# IPMC_MACP_2.net
KiCad netlist of a schematic drawn in Altium Designer
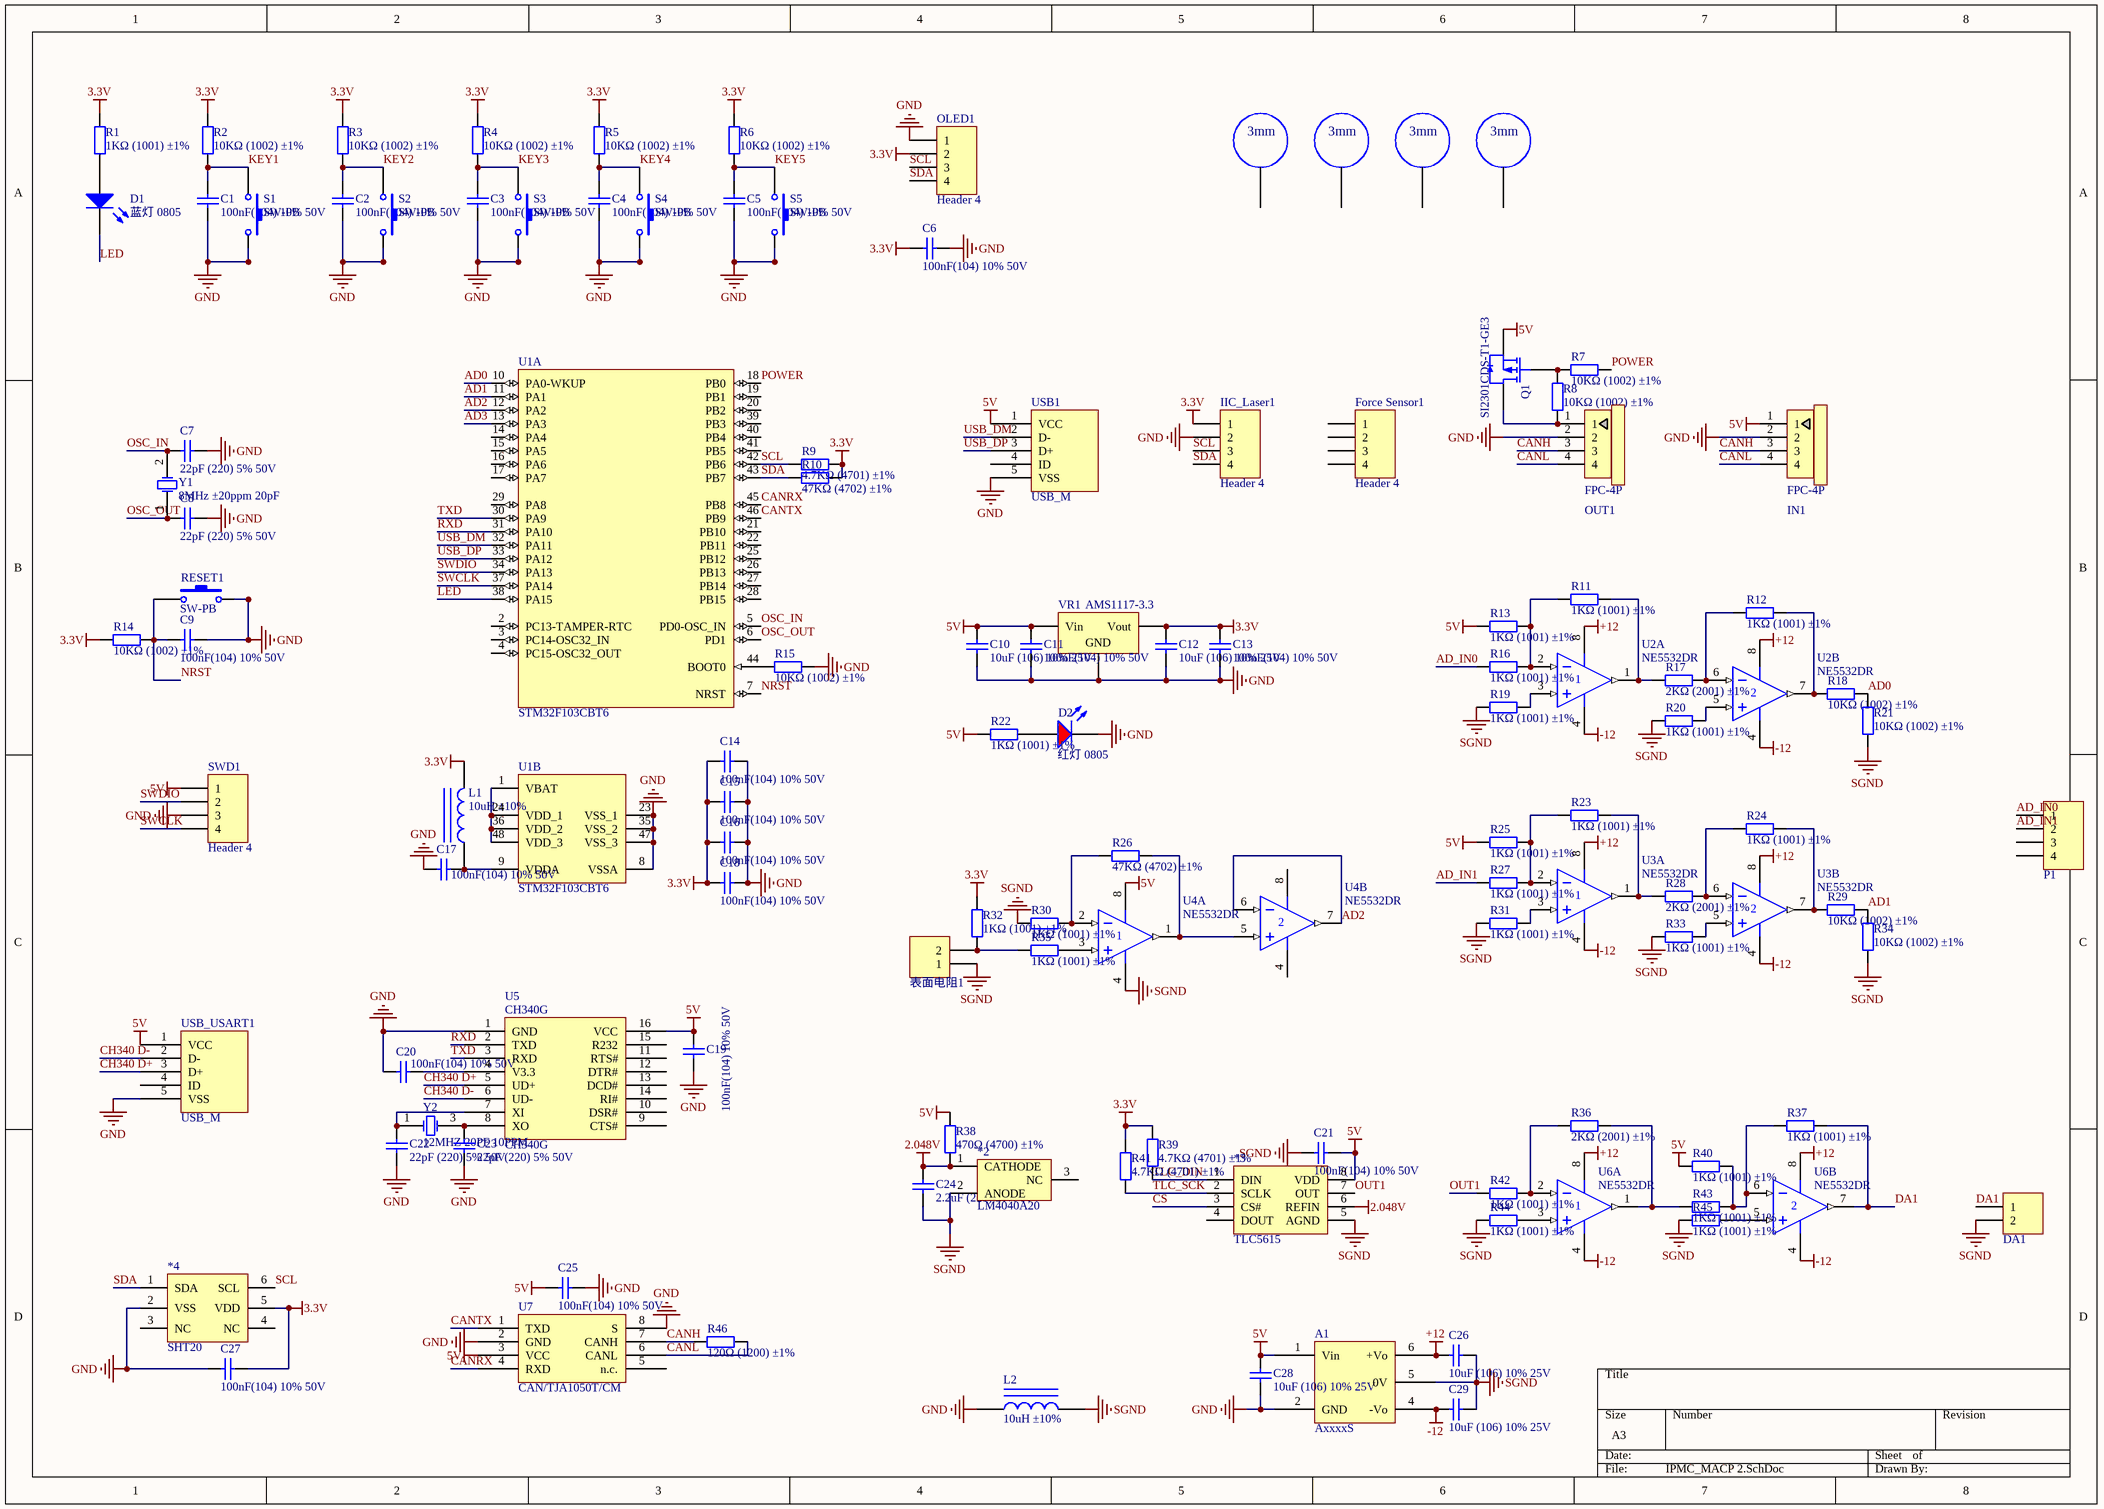
[diagram p0: IPMC_MACP 2.SchDoc]

(export (version "E")
  (design (tool "Eeschema 10.0.6"))
  (components
    (comp (ref "*2")
      (value "LM4040A20")
      (footprint "SOT-23")
      (description "2.048V基准电压芯片")
      (libsource (lib "fszhang") (part "LM4040A20"))
    )
    (comp (ref "*3")
      (value "TLC5615")
      (footprint "SOP-8")
      (description "单通道10bitDA数模转换器")
      (libsource (lib "fszhang") (part "TLC5615"))
    )
    (comp (ref "*4") (value "SHT20") (footprint "DFN6") (libsource (lib "fszhang") (part "SHT20")))
    (comp (ref "A1")
      (value "AxxxxS")
      (footprint "AxxxxS")
      (description "能达电源模块")
      (libsource (lib "fszhang") (part "AxxxxS"))
    )
    (comp (ref "C1")
      (value "100nF(104) 10% 50V")
      (footprint "0805_C")
      (description "贴片电容")
      (libsource (lib "Miscellaneous Devices LC") (part "0805 100nF(104) 10% 50V"))
    )
    (comp (ref "C2")
      (value "100nF(104) 10% 50V")
      (footprint "0805_C")
      (description "贴片电容")
      (libsource (lib "Miscellaneous Devices LC") (part "0805 100nF(104) 10% 50V"))
    )
    (comp (ref "C3")
      (value "100nF(104) 10% 50V")
      (footprint "0805_C")
      (description "贴片电容")
      (libsource (lib "Miscellaneous Devices LC") (part "0805 100nF(104) 10% 50V"))
    )
    (comp (ref "C4")
      (value "100nF(104) 10% 50V")
      (footprint "0805_C")
      (description "贴片电容")
      (libsource (lib "Miscellaneous Devices LC") (part "0805 100nF(104) 10% 50V"))
    )
    (comp (ref "C5")
      (value "100nF(104) 10% 50V")
      (footprint "0805_C")
      (description "贴片电容")
      (libsource (lib "Miscellaneous Devices LC") (part "0805 100nF(104) 10% 50V"))
    )
    (comp (ref "C6")
      (value "100nF(104) 10% 50V")
      (footprint "0805_C")
      (description "贴片电容")
      (libsource (lib "Miscellaneous Devices LC") (part "0805 100nF(104) 10% 50V"))
    )
    (comp (ref "C7")
      (value "22pF (220) 5% 50V")
      (footprint "0805_C")
      (description "贴片电容")
      (libsource (lib "Miscellaneous Devices LC") (part "0805 22pF (220) 5% 50V"))
    )
    (comp (ref "C8")
      (value "22pF (220) 5% 50V")
      (footprint "0805_C")
      (description "贴片电容")
      (libsource (lib "Miscellaneous Devices LC") (part "0805 22pF (220) 5% 50V"))
    )
    (comp (ref "C9")
      (value "100nF(104) 10% 50V")
      (footprint "0805_C")
      (description "贴片电容")
      (libsource (lib "Miscellaneous Devices LC") (part "0805 100nF(104) 10% 50V"))
    )
    (comp (ref "C10")
      (value "10uF (106) 10% 25V")
      (footprint "0805_C")
      (description "贴片电容")
      (libsource (lib "Miscellaneous Devices LC") (part "0805 10uF (106) 10% 25V"))
    )
    (comp (ref "C11")
      (value "100nF(104) 10% 50V")
      (footprint "0805_C")
      (description "贴片电容")
      (libsource (lib "Miscellaneous Devices LC") (part "0805 100nF(104) 10% 50V"))
    )
    (comp (ref "C12")
      (value "10uF (106) 10% 25V")
      (footprint "0805_C")
      (description "贴片电容")
      (libsource (lib "Miscellaneous Devices LC") (part "0805 10uF (106) 10% 25V"))
    )
    (comp (ref "C13")
      (value "100nF(104) 10% 50V")
      (footprint "0805_C")
      (description "贴片电容")
      (libsource (lib "Miscellaneous Devices LC") (part "0805 100nF(104) 10% 50V"))
    )
    (comp (ref "C14")
      (value "100nF(104) 10% 50V")
      (footprint "0805_C")
      (description "贴片电容")
      (libsource (lib "Miscellaneous Devices LC") (part "0805 100nF(104) 10% 50V"))
    )
    (comp (ref "C15")
      (value "100nF(104) 10% 50V")
      (footprint "0805_C")
      (description "贴片电容")
      (libsource (lib "Miscellaneous Devices LC") (part "0805 100nF(104) 10% 50V"))
    )
    (comp (ref "C16")
      (value "100nF(104) 10% 50V")
      (footprint "0805_C")
      (description "贴片电容")
      (libsource (lib "Miscellaneous Devices LC") (part "0805 100nF(104) 10% 50V"))
    )
    (comp (ref "C17")
      (value "100nF(104) 10% 50V")
      (footprint "0805_C")
      (description "贴片电容")
      (libsource (lib "Miscellaneous Devices LC") (part "0805 100nF(104) 10% 50V"))
    )
    (comp (ref "C18")
      (value "100nF(104) 10% 50V")
      (footprint "0805_C")
      (description "贴片电容")
      (libsource (lib "Miscellaneous Devices LC") (part "0805 100nF(104) 10% 50V"))
    )
    (comp (ref "C19")
      (value "100nF(104) 10% 50V")
      (footprint "0805_C")
      (description "贴片电容")
      (libsource (lib "Miscellaneous Devices LC") (part "0805 100nF(104) 10% 50V"))
    )
    (comp (ref "C20")
      (value "100nF(104) 10% 50V")
      (footprint "0805_C")
      (description "贴片电容")
      (libsource (lib "Miscellaneous Devices LC") (part "0805 100nF(104) 10% 50V"))
    )
    (comp (ref "C21")
      (value "100nF(104) 10% 50V")
      (footprint "0805_C")
      (description "贴片电容")
      (libsource (lib "Miscellaneous Devices LC") (part "0805 100nF(104) 10% 50V"))
    )
    (comp (ref "C22")
      (value "22pF (220) 5% 50V")
      (footprint "0805_C")
      (description "贴片电容")
      (libsource (lib "Miscellaneous Devices LC") (part "0805 22pF (220) 5% 50V"))
    )
    (comp (ref "C23")
      (value "22pF (220) 5% 50V")
      (footprint "0805_C")
      (description "贴片电容")
      (libsource (lib "Miscellaneous Devices LC") (part "0805 22pF (220) 5% 50V"))
    )
    (comp (ref "C24")
      (value "2.2uF (225) 20% 50V")
      (footprint "0805_C")
      (description "贴片电容")
      (libsource (lib "Miscellaneous Devices LC") (part "0805 2.2uF (225) 20% 50V"))
    )
    (comp (ref "C25")
      (value "100nF(104) 10% 50V")
      (footprint "0805_C")
      (description "贴片电容")
      (libsource (lib "Miscellaneous Devices LC") (part "0805 100nF(104) 10% 50V"))
    )
    (comp (ref "C26")
      (value "10uF (106) 10% 25V")
      (footprint "0805_C")
      (description "贴片电容")
      (libsource (lib "Miscellaneous Devices LC") (part "0805 10uF (106) 10% 25V"))
    )
    (comp (ref "C27")
      (value "100nF(104) 10% 50V")
      (footprint "0805_C")
      (description "贴片电容")
      (libsource (lib "Miscellaneous Devices LC") (part "0805 100nF(104) 10% 50V"))
    )
    (comp (ref "C28")
      (value "10uF (106) 10% 25V")
      (footprint "0805_C")
      (description "贴片电容")
      (libsource (lib "Miscellaneous Devices LC") (part "0805 10uF (106) 10% 25V"))
    )
    (comp (ref "C29")
      (value "10uF (106) 10% 25V")
      (footprint "0805_C")
      (description "贴片电容")
      (libsource (lib "Miscellaneous Devices LC") (part "0805 10uF (106) 10% 25V"))
    )
    (comp (ref "D1")
      (value "蓝灯 0805")
      (footprint "0805_LED_S1")
      (description "发光二极管")
      (libsource (lib "Miscellaneous Devices LC") (part "0805 蓝灯"))
    )
    (comp (ref "D2")
      (value "红灯 0805")
      (footprint "0805_LED_S1")
      (description "发光二极管")
      (libsource (lib "Miscellaneous Devices LC") (part "0805 红灯"))
    )
    (comp (ref "DA1")
      (value "Header 2")
      (footprint "HDR2X1_A")
      (description "接插件")
      (libsource (lib "fszhang") (part "Header 2"))
    )
    (comp (ref "Force Sensor1")
      (value "Header 4")
      (footprint "HDR1X4")
      (description "Header, 4-Pin")
      (libsource (lib "Miscellaneous Connectors") (part "Header 4"))
    )
    (comp (ref "IIC_Laser1")
      (value "Header 4")
      (footprint "HDR1X4")
      (description "Header, 4-Pin")
      (libsource (lib "Miscellaneous Connectors") (part "Header 4"))
    )
    (comp (ref "IN1")
      (value "FPC-4P")
      (footprint "FPC1.0-4P-A")
      (description "FPC排线连接器")
      (libsource (lib "fszhang") (part "FPC-4P"))
    )
    (comp (ref "L1")
      (value "10uH ±10%")
      (footprint "0805_L")
      (description "贴片电感")
      (libsource (lib "Miscellaneous Devices LC") (part "0805 10uH 10%"))
    )
    (comp (ref "L2")
      (value "10uH ±10%")
      (footprint "0805_L")
      (description "贴片电感")
      (libsource (lib "Miscellaneous Devices LC") (part "0805 10uH 10%"))
    )
    (comp (ref "OLED1")
      (value "Header 4")
      (footprint "HDR1X4")
      (description "Header, 4-Pin")
      (libsource (lib "Miscellaneous Connectors") (part "Header 4"))
    )
    (comp (ref "OUT1")
      (value "FPC-4P")
      (footprint "FPC1.0-4P-A")
      (description "FPC排线连接器")
      (libsource (lib "fszhang") (part "FPC-4P"))
    )
    (comp (ref "P1")
      (value "Header 4")
      (footprint "HDR4X1_A")
      (description "接插件")
      (libsource (lib "fszhang") (part "Header 4"))
    )
    (comp (ref "Q1")
      (value "SI2301CDS-T1-GE3")
      (footprint "SOT-23(SOT-23-3)")
      (description "MOS(场效应管)")
      (libsource (lib "Miscellaneous Devices LC") (part "SI2301CDS-T1-GE3"))
    )
    (comp (ref "R1")
      (value "1KΩ (1001) ±1%")
      (footprint "0805_R")
      (description "贴片电阻")
      (libsource (lib "") (part "0805 1KΩ (1001) 1%_1"))
    )
    (comp (ref "R2")
      (value "10KΩ (1002) ±1%")
      (footprint "0805_R")
      (description "贴片电阻")
      (libsource (lib "Miscellaneous Devices LC") (part "0805 10KΩ (1002) 1%"))
    )
    (comp (ref "R3")
      (value "10KΩ (1002) ±1%")
      (footprint "0805_R")
      (description "贴片电阻")
      (libsource (lib "Miscellaneous Devices LC") (part "0805 10KΩ (1002) 1%"))
    )
    (comp (ref "R4")
      (value "10KΩ (1002) ±1%")
      (footprint "0805_R")
      (description "贴片电阻")
      (libsource (lib "Miscellaneous Devices LC") (part "0805 10KΩ (1002) 1%"))
    )
    (comp (ref "R5")
      (value "10KΩ (1002) ±1%")
      (footprint "0805_R")
      (description "贴片电阻")
      (libsource (lib "Miscellaneous Devices LC") (part "0805 10KΩ (1002) 1%"))
    )
    (comp (ref "R6")
      (value "10KΩ (1002) ±1%")
      (footprint "0805_R")
      (description "贴片电阻")
      (libsource (lib "Miscellaneous Devices LC") (part "0805 10KΩ (1002) 1%"))
    )
    (comp (ref "R7")
      (value "10KΩ (1002) ±1%")
      (footprint "0805_R")
      (description "贴片电阻")
      (libsource (lib "") (part "0805 10KΩ (1002) 1%_1"))
    )
    (comp (ref "R8")
      (value "10KΩ (1002) ±1%")
      (footprint "0805_R")
      (description "贴片电阻")
      (libsource (lib "Miscellaneous Devices LC") (part "0805 10KΩ (1002) 1%"))
    )
    (comp (ref "R9")
      (value "4.7KΩ (4701) ±1%")
      (footprint "0805_R")
      (description "贴片电阻")
      (libsource (lib "") (part "0805 4.7KΩ (4701) 1%_1"))
    )
    (comp (ref "R10")
      (value "47KΩ (4702) ±1%")
      (footprint "0805_R")
      (description "贴片电阻")
      (libsource (lib "Miscellaneous Devices LC") (part "0805 47KΩ (4702) 1%"))
    )
    (comp (ref "R11")
      (value "1KΩ (1001) ±1%")
      (footprint "0805_R")
      (description "贴片电阻")
      (libsource (lib "") (part "0805 1KΩ (1001) 1%_2"))
    )
    (comp (ref "R12")
      (value "1KΩ (1001) ±1%")
      (footprint "0805_R")
      (description "贴片电阻")
      (libsource (lib "") (part "0805 1KΩ (1001) 1%_2"))
    )
    (comp (ref "R13")
      (value "1KΩ (1001) ±1%")
      (footprint "0805_R")
      (description "贴片电阻")
      (libsource (lib "") (part "0805 1KΩ (1001) 1%_2"))
    )
    (comp (ref "R14")
      (value "10KΩ (1002) ±1%")
      (footprint "0805_R")
      (description "贴片电阻")
      (libsource (lib "") (part "0805 10KΩ (1002) 1%_1"))
    )
    (comp (ref "R15")
      (value "10KΩ (1002) ±1%")
      (footprint "0805_R")
      (description "贴片电阻")
      (libsource (lib "") (part "0805 10KΩ (1002) 1%_1"))
    )
    (comp (ref "R16")
      (value "1KΩ (1001) ±1%")
      (footprint "0805_R")
      (description "贴片电阻")
      (libsource (lib "") (part "0805 1KΩ (1001) 1%_2"))
    )
    (comp (ref "R17")
      (value "2KΩ (2001) ±1%")
      (footprint "0805_R")
      (description "贴片电阻")
      (libsource (lib "Miscellaneous Devices LC") (part "0805 2KΩ (2001) 1%"))
    )
    (comp (ref "R18")
      (value "10KΩ (1002) ±1%")
      (footprint "0805_R")
      (description "贴片电阻")
      (libsource (lib "") (part "0805 10KΩ (1002) 1%_1"))
    )
    (comp (ref "R19")
      (value "1KΩ (1001) ±1%")
      (footprint "0805_R")
      (description "贴片电阻")
      (libsource (lib "") (part "0805 1KΩ (1001) 1%_2"))
    )
    (comp (ref "R20")
      (value "1KΩ (1001) ±1%")
      (footprint "0805_R")
      (description "贴片电阻")
      (libsource (lib "") (part "0805 1KΩ (1001) 1%_2"))
    )
    (comp (ref "R21")
      (value "10KΩ (1002) ±1%")
      (footprint "0805_R")
      (description "贴片电阻")
      (libsource (lib "") (part "0805 10KΩ (1002) 1%_2"))
    )
    (comp (ref "R22")
      (value "1KΩ (1001) ±1%")
      (footprint "0805_R")
      (description "贴片电阻")
      (libsource (lib "Miscellaneous Devices LC") (part "0805 1KΩ (1001) 1%"))
    )
    (comp (ref "R23")
      (value "1KΩ (1001) ±1%")
      (footprint "0805_R")
      (description "贴片电阻")
      (libsource (lib "") (part "0805 1KΩ (1001) 1%_2"))
    )
    (comp (ref "R24")
      (value "1KΩ (1001) ±1%")
      (footprint "0805_R")
      (description "贴片电阻")
      (libsource (lib "") (part "0805 1KΩ (1001) 1%_2"))
    )
    (comp (ref "R25")
      (value "1KΩ (1001) ±1%")
      (footprint "0805_R")
      (description "贴片电阻")
      (libsource (lib "") (part "0805 1KΩ (1001) 1%_2"))
    )
    (comp (ref "R26")
      (value "47KΩ (4702) ±1%")
      (footprint "0805_R")
      (description "贴片电阻")
      (libsource (lib "Miscellaneous Devices LC") (part "0805 47KΩ (4702) 1%"))
    )
    (comp (ref "R27")
      (value "1KΩ (1001) ±1%")
      (footprint "0805_R")
      (description "贴片电阻")
      (libsource (lib "") (part "0805 1KΩ (1001) 1%_2"))
    )
    (comp (ref "R28")
      (value "2KΩ (2001) ±1%")
      (footprint "0805_R")
      (description "贴片电阻")
      (libsource (lib "Miscellaneous Devices LC") (part "0805 2KΩ (2001) 1%"))
    )
    (comp (ref "R29")
      (value "10KΩ (1002) ±1%")
      (footprint "0805_R")
      (description "贴片电阻")
      (libsource (lib "") (part "0805 10KΩ (1002) 1%_1"))
    )
    (comp (ref "R30")
      (value "1KΩ (1001) ±1%")
      (footprint "0805_R")
      (description "贴片电阻")
      (libsource (lib "Miscellaneous Devices LC") (part "0805 1KΩ (1001) 1%"))
    )
    (comp (ref "R31")
      (value "1KΩ (1001) ±1%")
      (footprint "0805_R")
      (description "贴片电阻")
      (libsource (lib "") (part "0805 1KΩ (1001) 1%_2"))
    )
    (comp (ref "R32")
      (value "1KΩ (1001) ±1%")
      (footprint "0805_R")
      (description "贴片电阻")
      (libsource (lib "") (part "0805 1KΩ (1001) 1%_1"))
    )
    (comp (ref "R33")
      (value "1KΩ (1001) ±1%")
      (footprint "0805_R")
      (description "贴片电阻")
      (libsource (lib "") (part "0805 1KΩ (1001) 1%_2"))
    )
    (comp (ref "R34")
      (value "10KΩ (1002) ±1%")
      (footprint "0805_R")
      (description "贴片电阻")
      (libsource (lib "") (part "0805 10KΩ (1002) 1%_2"))
    )
    (comp (ref "R35")
      (value "1KΩ (1001) ±1%")
      (footprint "0805_R")
      (description "贴片电阻")
      (libsource (lib "Miscellaneous Devices LC") (part "0805 1KΩ (1001) 1%"))
    )
    (comp (ref "R36")
      (value "2KΩ (2001) ±1%")
      (footprint "0805_R")
      (description "贴片电阻")
      (libsource (lib "Miscellaneous Devices LC") (part "0805 2KΩ (2001) 1%"))
    )
    (comp (ref "R37")
      (value "1KΩ (1001) ±1%")
      (footprint "0805_R")
      (description "贴片电阻")
      (libsource (lib "") (part "0805 1KΩ (1001) 1%_2"))
    )
    (comp (ref "R38")
      (value "470Ω (4700) ±1%")
      (footprint "0805_R")
      (description "贴片电阻")
      (libsource (lib "Miscellaneous Devices LC") (part "0805 470Ω (4700) 1%"))
    )
    (comp (ref "R39")
      (value "4.7KΩ (4701) ±1%")
      (footprint "0805_R")
      (description "贴片电阻")
      (libsource (lib "Miscellaneous Devices LC") (part "0805 4.7KΩ (4701) 1%"))
    )
    (comp (ref "R40")
      (value "1KΩ (1001) ±1%")
      (footprint "0805_R")
      (description "贴片电阻")
      (libsource (lib "") (part "0805 1KΩ (1001) 1%_2"))
    )
    (comp (ref "R41")
      (value "4.7KΩ (4701) ±1%")
      (footprint "0805_R")
      (description "贴片电阻")
      (libsource (lib "Miscellaneous Devices LC") (part "0805 4.7KΩ (4701) 1%"))
    )
    (comp (ref "R42")
      (value "1KΩ (1001) ±1%")
      (footprint "0805_R")
      (description "贴片电阻")
      (libsource (lib "") (part "0805 1KΩ (1001) 1%_2"))
    )
    (comp (ref "R43")
      (value "1KΩ (1001) ±1%")
      (footprint "0805_R")
      (description "贴片电阻")
      (libsource (lib "") (part "0805 1KΩ (1001) 1%_2"))
    )
    (comp (ref "R44")
      (value "1KΩ (1001) ±1%")
      (footprint "0805_R")
      (description "贴片电阻")
      (libsource (lib "") (part "0805 1KΩ (1001) 1%_2"))
    )
    (comp (ref "R45")
      (value "1KΩ (1001) ±1%")
      (footprint "0805_R")
      (description "贴片电阻")
      (libsource (lib "") (part "0805 1KΩ (1001) 1%_2"))
    )
    (comp (ref "R46")
      (value "120Ω (1200) ±1%")
      (footprint "0805_R")
      (description "贴片电阻")
      (libsource (lib "Miscellaneous Devices LC") (part "0805 120Ω (1200) 1%"))
    )
    (comp (ref "RESET1")
      (value "SW-PB")
      (footprint "SW_PB2_A1")
      (description "微动开关")
      (libsource (lib "fszhang") (part "SW-PB"))
    )
    (comp (ref "S1")
      (value "SW-PB")
      (footprint "SW_PB2_A1")
      (description "微动开关")
      (libsource (lib "fszhang") (part "SW-PB"))
    )
    (comp (ref "S2")
      (value "SW-PB")
      (footprint "SW_PB2_A1")
      (description "微动开关")
      (libsource (lib "fszhang") (part "SW-PB"))
    )
    (comp (ref "S3")
      (value "SW-PB")
      (footprint "SW_PB2_A1")
      (description "微动开关")
      (libsource (lib "fszhang") (part "SW-PB"))
    )
    (comp (ref "S4")
      (value "SW-PB")
      (footprint "SW_PB2_A1")
      (description "微动开关")
      (libsource (lib "fszhang") (part "SW-PB"))
    )
    (comp (ref "S5")
      (value "SW-PB")
      (footprint "SW_PB2_A1")
      (description "微动开关")
      (libsource (lib "fszhang") (part "SW-PB"))
    )
    (comp (ref "SWD1")
      (value "Header 4")
      (footprint "HDR1X4")
      (description "Header, 4-Pin")
      (libsource (lib "Miscellaneous Connectors") (part "Header 4"))
    )
    (comp (ref "T1") (value "M3铜柱螺丝孔") (footprint "螺丝孔-3mm") (libsource (lib "fszhang") (part "M3铜柱螺丝孔")))
    (comp (ref "T2") (value "M3铜柱螺丝孔") (footprint "螺丝孔-3mm") (libsource (lib "fszhang") (part "M3铜柱螺丝孔")))
    (comp (ref "T3") (value "M3铜柱螺丝孔") (footprint "螺丝孔-3mm") (libsource (lib "fszhang") (part "M3铜柱螺丝孔")))
    (comp (ref "T4") (value "M3铜柱螺丝孔") (footprint "螺丝孔-3mm") (libsource (lib "fszhang") (part "M3铜柱螺丝孔")))
    (comp (ref "U1")
      (value "STM32F103CBT6")
      (footprint "LQFP-48_7x7x05P")
      (description "ARM")
      (libsource (lib "Miscellaneous Devices LC") (part "STM32F103CBT6"))
    )
    (comp (ref "U2")
      (value "NE5532DR")
      (footprint "SOIC-8_150mil")
      (description "功放")
      (libsource (lib "Miscellaneous Devices LC") (part "NE5532DR"))
    )
    (comp (ref "U3")
      (value "NE5532DR")
      (footprint "SOIC-8_150mil")
      (description "功放")
      (libsource (lib "Miscellaneous Devices LC") (part "NE5532DR"))
    )
    (comp (ref "U4")
      (value "NE5532DR")
      (footprint "SOIC-8_150mil")
      (description "功放")
      (libsource (lib "Miscellaneous Devices LC") (part "NE5532DR"))
    )
    (comp (ref "U5")
      (value "CH340G")
      (footprint "SOIC-16_150mil")
      (description "USB")
      (libsource (lib "Miscellaneous Devices LC") (part "CH340G"))
    )
    (comp (ref "U6")
      (value "NE5532DR")
      (footprint "SOIC-8_150mil")
      (description "功放")
      (libsource (lib "Miscellaneous Devices LC") (part "NE5532DR"))
    )
    (comp (ref "U7")
      (value "CAN/TJA1050T/CM")
      (footprint "SOIC-8_150mil")
      (description "CAN")
      (libsource (lib "Miscellaneous Devices LC") (part "CAN/TJA1050T/CM"))
    )
    (comp (ref "USB1")
      (value "USB_M")
      (footprint "USB_MICRO")
      (description "MicroUSB接口")
      (libsource (lib "fszhang") (part "USB_M"))
    )
    (comp (ref "USB_USART1")
      (value "USB_M")
      (footprint "USB_MICRO")
      (description "MicroUSB接口")
      (libsource (lib "fszhang") (part "USB_M"))
    )
    (comp (ref "VR1")
      (value "AMS1117-3.3")
      (footprint "SOT-223")
      (description "低压差线性稳压(LDO)")
      (libsource (lib "Miscellaneous Devices LC") (part "SOT-223 AMS1117-3.3"))
    )
    (comp (ref "Y1")
      (value "8MHz ±20ppm 20pF")
      (footprint "SMD-5032_2P")
      (description "贴片晶振")
      (libsource (lib "Miscellaneous Devices LC") (part "SMD-5032_2P 8MHz 20ppm 20pF"))
    )
    (comp (ref "Y2")
      (value "12MHZ 20PF 10PPM")
      (footprint "SMD-3225_4P")
      (description "贴片晶振")
      (libsource (lib "Miscellaneous Devices LC") (part "SMD-3225_4P  12MHZ 20PF 10PPM"))
    )
    (comp (ref "表面电阻1")
      (value "Header 2")
      (footprint "HDR2X1_A")
      (description "接插件")
      (libsource (lib "") (part "Header 2_1"))
    )
  )
  (nets
    (net (code "1") (name "+12") (class "Default")
      (node (ref "A1") (pin "6") (pinfunction "+Vo_6") (pintype "passive"))
      (node (ref "C26") (pin "1") (pinfunction "1_1") (pintype "passive"))
      (node (ref "U2") (pin "8") (pinfunction "V+_8") (pintype "power_in"))
      (node (ref "U3") (pin "8") (pinfunction "V+_8") (pintype "power_in"))
      (node (ref "U6") (pin "8") (pinfunction "V+_8") (pintype "power_in"))
    )
    (net (code "2") (name "-12") (class "Default")
      (node (ref "A1") (pin "4") (pinfunction "-Vo_4") (pintype "passive"))
      (node (ref "C29") (pin "1") (pinfunction "1_1") (pintype "passive"))
      (node (ref "U2") (pin "4") (pinfunction "V-_4") (pintype "power_in"))
      (node (ref "U3") (pin "4") (pinfunction "V-_4") (pintype "power_in"))
      (node (ref "U6") (pin "4") (pinfunction "V-_4") (pintype "power_in"))
    )
    (net (code "3") (name "/AD0") (class "Default")
      (node (ref "R18") (pin "2") (pinfunction "2_2") (pintype "passive"))
      (node (ref "R21") (pin "2") (pinfunction "2_2") (pintype "passive"))
      (node (ref "U1") (pin "10") (pinfunction "PA0-WKUP_10") (pintype "bidirectional"))
    )
    (net (code "4") (name "/AD1") (class "Default")
      (node (ref "R29") (pin "2") (pinfunction "2_2") (pintype "passive"))
      (node (ref "R34") (pin "2") (pinfunction "2_2") (pintype "passive"))
      (node (ref "U1") (pin "11") (pinfunction "PA1_11") (pintype "bidirectional"))
    )
    (net (code "5") (name "/AD2") (class "Default")
      (node (ref "U1") (pin "12") (pinfunction "PA2_12") (pintype "bidirectional"))
      (node (ref "U4") (pin "6") (pinfunction "IN-_6") (pintype "input"))
      (node (ref "U4") (pin "7") (pinfunction "OUT_7") (pintype "output"))
    )
    (net (code "6") (name "/AD3") (class "Default")
      (node (ref "U1") (pin "13") (pinfunction "PA3_13") (pintype "bidirectional"))
    )
    (net (code "7") (name "/AD_IN0") (class "Default")
      (node (ref "P1") (pin "1") (pinfunction "1_1") (pintype "passive"))
      (node (ref "R16") (pin "2") (pinfunction "2_2") (pintype "passive"))
    )
    (net (code "8") (name "/AD_IN1") (class "Default")
      (node (ref "P1") (pin "2") (pinfunction "2_2") (pintype "passive"))
      (node (ref "R27") (pin "2") (pinfunction "2_2") (pintype "passive"))
    )
    (net (code "9") (name "/CANH") (class "Default")
      (node (ref "IN1") (pin "3") (pinfunction "3_3") (pintype "passive"))
      (node (ref "OUT1") (pin "3") (pinfunction "3_3") (pintype "passive"))
      (node (ref "R46") (pin "1") (pinfunction "1_1") (pintype "passive"))
      (node (ref "U7") (pin "7") (pinfunction "CANH_7") (pintype "passive"))
    )
    (net (code "10") (name "/CANL") (class "Default")
      (node (ref "IN1") (pin "4") (pinfunction "4_4") (pintype "passive"))
      (node (ref "OUT1") (pin "4") (pinfunction "4_4") (pintype "passive"))
      (node (ref "R46") (pin "2") (pinfunction "2_2") (pintype "passive"))
      (node (ref "U7") (pin "6") (pinfunction "CANL_6") (pintype "passive"))
    )
    (net (code "11") (name "/CANRX") (class "Default")
      (node (ref "U1") (pin "45") (pinfunction "PB8_45") (pintype "bidirectional"))
      (node (ref "U7") (pin "4") (pinfunction "RXD_4") (pintype "passive"))
    )
    (net (code "12") (name "/CANTX") (class "Default")
      (node (ref "U1") (pin "46") (pinfunction "PB9_46") (pintype "bidirectional"))
      (node (ref "U7") (pin "1") (pinfunction "TXD_1") (pintype "passive"))
    )
    (net (code "13") (name "/CH340 D+") (class "Default")
      (node (ref "U5") (pin "5") (pinfunction "UD+_5") (pintype "passive"))
      (node (ref "USB_USART1") (pin "3") (pinfunction "D+_3") (pintype "passive"))
    )
    (net (code "14") (name "/CH340 D-") (class "Default")
      (node (ref "U5") (pin "6") (pinfunction "UD-_6") (pintype "passive"))
      (node (ref "USB_USART1") (pin "2") (pinfunction "D-_2") (pintype "passive"))
    )
    (net (code "15") (name "/CS") (class "Default")
      (node (ref "*3") (pin "3") (pinfunction "CS#_3") (pintype "passive"))
    )
    (net (code "16") (name "/DA1") (class "Default")
      (node (ref "DA1") (pin "1") (pinfunction "1_1") (pintype "passive"))
      (node (ref "R37") (pin "1") (pinfunction "1_1") (pintype "passive"))
      (node (ref "U6") (pin "7") (pinfunction "OUT_7") (pintype "output"))
    )
    (net (code "17") (name "/KEY1") (class "Default")
      (node (ref "C1") (pin "1") (pinfunction "1_1") (pintype "passive"))
      (node (ref "R2") (pin "2") (pinfunction "2_2") (pintype "passive"))
      (node (ref "S1") (pin "1") (pinfunction "1_1") (pintype "passive"))
    )
    (net (code "18") (name "/KEY2") (class "Default")
      (node (ref "C2") (pin "1") (pinfunction "1_1") (pintype "passive"))
      (node (ref "R3") (pin "2") (pinfunction "2_2") (pintype "passive"))
      (node (ref "S2") (pin "1") (pinfunction "1_1") (pintype "passive"))
    )
    (net (code "19") (name "/KEY3") (class "Default")
      (node (ref "C3") (pin "1") (pinfunction "1_1") (pintype "passive"))
      (node (ref "R4") (pin "2") (pinfunction "2_2") (pintype "passive"))
      (node (ref "S3") (pin "1") (pinfunction "1_1") (pintype "passive"))
    )
    (net (code "20") (name "/KEY4") (class "Default")
      (node (ref "C4") (pin "1") (pinfunction "1_1") (pintype "passive"))
      (node (ref "R5") (pin "2") (pinfunction "2_2") (pintype "passive"))
      (node (ref "S4") (pin "1") (pinfunction "1_1") (pintype "passive"))
    )
    (net (code "21") (name "/KEY5") (class "Default")
      (node (ref "C5") (pin "1") (pinfunction "1_1") (pintype "passive"))
      (node (ref "R6") (pin "2") (pinfunction "2_2") (pintype "passive"))
      (node (ref "S5") (pin "1") (pinfunction "1_1") (pintype "passive"))
    )
    (net (code "22") (name "/LED") (class "Default")
      (node (ref "D1") (pin "K") (pinfunction "K_K") (pintype "passive"))
      (node (ref "U1") (pin "38") (pinfunction "PA15_38") (pintype "bidirectional"))
    )
    (net (code "23") (name "/NRST") (class "Default")
      (node (ref "C9") (pin "1") (pinfunction "1_1") (pintype "passive"))
      (node (ref "R14") (pin "2") (pinfunction "2_2") (pintype "passive"))
      (node (ref "RESET1") (pin "1") (pinfunction "1_1") (pintype "passive"))
      (node (ref "U1") (pin "7") (pinfunction "NRST_7") (pintype "bidirectional"))
    )
    (net (code "24") (name "/OSC_IN") (class "Default")
      (node (ref "C7") (pin "2") (pinfunction "2_2") (pintype "passive"))
      (node (ref "U1") (pin "5") (pinfunction "PD0-OSC_IN_5") (pintype "bidirectional"))
      (node (ref "Y1") (pin "2") (pinfunction "OSC2_2") (pintype "passive"))
    )
    (net (code "25") (name "/OSC_OUT") (class "Default")
      (node (ref "C8") (pin "2") (pinfunction "2_2") (pintype "passive"))
      (node (ref "U1") (pin "6") (pinfunction "PD1_6") (pintype "bidirectional"))
      (node (ref "Y1") (pin "1") (pinfunction "OSC1_1") (pintype "passive"))
    )
    (net (code "26") (name "/OUT1") (class "Default")
      (node (ref "*3") (pin "7") (pinfunction "OUT_7") (pintype "passive"))
      (node (ref "R42") (pin "2") (pinfunction "2_2") (pintype "passive"))
    )
    (net (code "27") (name "/POWER") (class "Default")
      (node (ref "R7") (pin "2") (pinfunction "2_2") (pintype "passive"))
      (node (ref "U1") (pin "18") (pinfunction "PB0_18") (pintype "bidirectional"))
    )
    (net (code "28") (name "/RXD") (class "Default")
      (node (ref "U1") (pin "31") (pinfunction "PA10_31") (pintype "bidirectional"))
      (node (ref "U5") (pin "2") (pinfunction "TXD_2") (pintype "passive"))
    )
    (net (code "29") (name "/SCL") (class "Default")
      (node (ref "*4") (pin "6") (pinfunction "SCL_6") (pintype "passive"))
      (node (ref "IIC_Laser1") (pin "3") (pinfunction "3_3") (pintype "passive"))
      (node (ref "OLED1") (pin "3") (pinfunction "3_3") (pintype "passive"))
      (node (ref "R9") (pin "1") (pinfunction "1_1") (pintype "passive"))
      (node (ref "U1") (pin "42") (pinfunction "PB6_42") (pintype "bidirectional"))
    )
    (net (code "30") (name "/SDA") (class "Default")
      (node (ref "*4") (pin "1") (pinfunction "SDA_1") (pintype "passive"))
      (node (ref "IIC_Laser1") (pin "4") (pinfunction "4_4") (pintype "passive"))
      (node (ref "OLED1") (pin "4") (pinfunction "4_4") (pintype "passive"))
      (node (ref "R10") (pin "1") (pinfunction "1_1") (pintype "passive"))
      (node (ref "U1") (pin "43") (pinfunction "PB7_43") (pintype "bidirectional"))
    )
    (net (code "31") (name "/SWCLK") (class "Default")
      (node (ref "SWD1") (pin "4") (pinfunction "4_4") (pintype "passive"))
      (node (ref "U1") (pin "37") (pinfunction "PA14_37") (pintype "bidirectional"))
    )
    (net (code "32") (name "/SWDIO") (class "Default")
      (node (ref "SWD1") (pin "2") (pinfunction "2_2") (pintype "passive"))
      (node (ref "U1") (pin "34") (pinfunction "PA13_34") (pintype "bidirectional"))
    )
    (net (code "33") (name "/TLC_DIN") (class "Default")
      (node (ref "*3") (pin "1") (pinfunction "DIN_1") (pintype "passive"))
      (node (ref "R39") (pin "1") (pinfunction "1_1") (pintype "passive"))
    )
    (net (code "34") (name "/TLC_SCK") (class "Default")
      (node (ref "*3") (pin "2") (pinfunction "SCLK_2") (pintype "passive"))
      (node (ref "R41") (pin "1") (pinfunction "1_1") (pintype "passive"))
    )
    (net (code "35") (name "/TXD") (class "Default")
      (node (ref "U1") (pin "30") (pinfunction "PA9_30") (pintype "bidirectional"))
      (node (ref "U5") (pin "3") (pinfunction "RXD_3") (pintype "passive"))
    )
    (net (code "36") (name "/USB_DM") (class "Default")
      (node (ref "U1") (pin "32") (pinfunction "PA11_32") (pintype "bidirectional"))
      (node (ref "USB1") (pin "2") (pinfunction "D-_2") (pintype "passive"))
    )
    (net (code "37") (name "/USB_DP") (class "Default")
      (node (ref "U1") (pin "33") (pinfunction "PA12_33") (pintype "bidirectional"))
      (node (ref "USB1") (pin "3") (pinfunction "D+_3") (pintype "passive"))
    )
    (net (code "38") (name "2.048V") (class "Default")
      (node (ref "*2") (pin "1") (pinfunction "CATHODE_1") (pintype "passive"))
      (node (ref "*3") (pin "6") (pinfunction "REFIN_6") (pintype "passive"))
      (node (ref "C24") (pin "2") (pinfunction "2_2") (pintype "passive"))
      (node (ref "R38") (pin "1") (pinfunction "1_1") (pintype "passive"))
    )
    (net (code "39") (name "3.3V") (class "Default")
      (node (ref "*4") (pin "5") (pinfunction "VDD_5") (pintype "passive"))
      (node (ref "C12") (pin "2") (pinfunction "2_2") (pintype "passive"))
      (node (ref "C13") (pin "2") (pinfunction "2_2") (pintype "passive"))
      (node (ref "C14") (pin "2") (pinfunction "2_2") (pintype "passive"))
      (node (ref "C15") (pin "2") (pinfunction "2_2") (pintype "passive"))
      (node (ref "C16") (pin "2") (pinfunction "2_2") (pintype "passive"))
      (node (ref "C18") (pin "2") (pinfunction "2_2") (pintype "passive"))
      (node (ref "C27") (pin "2") (pinfunction "2_2") (pintype "passive"))
      (node (ref "C6") (pin "2") (pinfunction "2_2") (pintype "passive"))
      (node (ref "IIC_Laser1") (pin "1") (pinfunction "1_1") (pintype "passive"))
      (node (ref "L1") (pin "2") (pinfunction "2_2") (pintype "passive"))
      (node (ref "OLED1") (pin "2") (pinfunction "2_2") (pintype "passive"))
      (node (ref "R1") (pin "1") (pinfunction "1_1") (pintype "passive"))
      (node (ref "R10") (pin "2") (pinfunction "2_2") (pintype "passive"))
      (node (ref "R14") (pin "1") (pinfunction "1_1") (pintype "passive"))
      (node (ref "R2") (pin "1") (pinfunction "1_1") (pintype "passive"))
      (node (ref "R3") (pin "1") (pinfunction "1_1") (pintype "passive"))
      (node (ref "R32") (pin "1") (pinfunction "1_1") (pintype "passive"))
      (node (ref "R39") (pin "2") (pinfunction "2_2") (pintype "passive"))
      (node (ref "R4") (pin "1") (pinfunction "1_1") (pintype "passive"))
      (node (ref "R41") (pin "2") (pinfunction "2_2") (pintype "passive"))
      (node (ref "R5") (pin "1") (pinfunction "1_1") (pintype "passive"))
      (node (ref "R6") (pin "1") (pinfunction "1_1") (pintype "passive"))
      (node (ref "R9") (pin "2") (pinfunction "2_2") (pintype "passive"))
      (node (ref "VR1") (pin "2") (pinfunction "Vout_2") (pintype "passive"))
    )
    (net (code "40") (name "5V") (class "Default")
      (node (ref "*3") (pin "8") (pinfunction "VDD_8") (pintype "passive"))
      (node (ref "A1") (pin "1") (pinfunction "Vin_1") (pintype "passive"))
      (node (ref "C10") (pin "2") (pinfunction "2_2") (pintype "passive"))
      (node (ref "C11") (pin "2") (pinfunction "2_2") (pintype "passive"))
      (node (ref "C19") (pin "2") (pinfunction "2_2") (pintype "passive"))
      (node (ref "C21") (pin "1") (pinfunction "1_1") (pintype "passive"))
      (node (ref "C25") (pin "2") (pinfunction "2_2") (pintype "passive"))
      (node (ref "C28") (pin "2") (pinfunction "2_2") (pintype "passive"))
      (node (ref "IN1") (pin "1") (pinfunction "1_1") (pintype "passive"))
      (node (ref "Q1") (pin "2") (pinfunction "S_2") (pintype "passive"))
      (node (ref "R13") (pin "2") (pinfunction "2_2") (pintype "passive"))
      (node (ref "R22") (pin "1") (pinfunction "1_1") (pintype "passive"))
      (node (ref "R25") (pin "2") (pinfunction "2_2") (pintype "passive"))
      (node (ref "R38") (pin "2") (pinfunction "2_2") (pintype "passive"))
      (node (ref "R40") (pin "2") (pinfunction "2_2") (pintype "passive"))
      (node (ref "SWD1") (pin "1") (pinfunction "1_1") (pintype "passive"))
      (node (ref "U4") (pin "8") (pinfunction "V+_8") (pintype "power_in"))
      (node (ref "U5") (pin "16") (pinfunction "VCC_16") (pintype "passive"))
      (node (ref "U7") (pin "3") (pinfunction "VCC_3") (pintype "passive"))
      (node (ref "USB1") (pin "1") (pinfunction "VCC_1") (pintype "passive"))
      (node (ref "USB_USART1") (pin "1") (pinfunction "VCC_1") (pintype "passive"))
      (node (ref "VR1") (pin "3") (pinfunction "Vin_3") (pintype "passive"))
    )
    (net (code "41") (name "GND") (class "Default")
      (node (ref "*4") (pin "2") (pinfunction "VSS_2") (pintype "passive"))
      (node (ref "A1") (pin "2") (pinfunction "GND_2") (pintype "passive"))
      (node (ref "C1") (pin "2") (pinfunction "2_2") (pintype "passive"))
      (node (ref "C10") (pin "1") (pinfunction "1_1") (pintype "passive"))
      (node (ref "C11") (pin "1") (pinfunction "1_1") (pintype "passive"))
      (node (ref "C12") (pin "1") (pinfunction "1_1") (pintype "passive"))
      (node (ref "C13") (pin "1") (pinfunction "1_1") (pintype "passive"))
      (node (ref "C14") (pin "1") (pinfunction "1_1") (pintype "passive"))
      (node (ref "C15") (pin "1") (pinfunction "1_1") (pintype "passive"))
      (node (ref "C16") (pin "1") (pinfunction "1_1") (pintype "passive"))
      (node (ref "C17") (pin "1") (pinfunction "1_1") (pintype "passive"))
      (node (ref "C18") (pin "1") (pinfunction "1_1") (pintype "passive"))
      (node (ref "C19") (pin "1") (pinfunction "1_1") (pintype "passive"))
      (node (ref "C2") (pin "2") (pinfunction "2_2") (pintype "passive"))
      (node (ref "C20") (pin "2") (pinfunction "2_2") (pintype "passive"))
      (node (ref "C22") (pin "1") (pinfunction "1_1") (pintype "passive"))
      (node (ref "C23") (pin "1") (pinfunction "1_1") (pintype "passive"))
      (node (ref "C25") (pin "1") (pinfunction "1_1") (pintype "passive"))
      (node (ref "C27") (pin "1") (pinfunction "1_1") (pintype "passive"))
      (node (ref "C28") (pin "1") (pinfunction "1_1") (pintype "passive"))
      (node (ref "C3") (pin "2") (pinfunction "2_2") (pintype "passive"))
      (node (ref "C4") (pin "2") (pinfunction "2_2") (pintype "passive"))
      (node (ref "C5") (pin "2") (pinfunction "2_2") (pintype "passive"))
      (node (ref "C6") (pin "1") (pinfunction "1_1") (pintype "passive"))
      (node (ref "C7") (pin "1") (pinfunction "1_1") (pintype "passive"))
      (node (ref "C8") (pin "1") (pinfunction "1_1") (pintype "passive"))
      (node (ref "C9") (pin "2") (pinfunction "2_2") (pintype "passive"))
      (node (ref "D2") (pin "K") (pinfunction "K_K") (pintype "passive"))
      (node (ref "IIC_Laser1") (pin "2") (pinfunction "2_2") (pintype "passive"))
      (node (ref "IN1") (pin "2") (pinfunction "2_2") (pintype "passive"))
      (node (ref "L2") (pin "1") (pinfunction "1_1") (pintype "passive"))
      (node (ref "OLED1") (pin "1") (pinfunction "1_1") (pintype "passive"))
      (node (ref "OUT1") (pin "2") (pinfunction "2_2") (pintype "passive"))
      (node (ref "R15") (pin "2") (pinfunction "2_2") (pintype "passive"))
      (node (ref "RESET1") (pin "2") (pinfunction "2_2") (pintype "passive"))
      (node (ref "S1") (pin "2") (pinfunction "2_2") (pintype "passive"))
      (node (ref "S2") (pin "2") (pinfunction "2_2") (pintype "passive"))
      (node (ref "S3") (pin "2") (pinfunction "2_2") (pintype "passive"))
      (node (ref "S4") (pin "2") (pinfunction "2_2") (pintype "passive"))
      (node (ref "S5") (pin "2") (pinfunction "2_2") (pintype "passive"))
      (node (ref "SWD1") (pin "3") (pinfunction "3_3") (pintype "passive"))
      (node (ref "U1") (pin "23") (pinfunction "VSS_1_23") (pintype "power_in"))
      (node (ref "U1") (pin "35") (pinfunction "VSS_2_35") (pintype "power_in"))
      (node (ref "U1") (pin "47") (pinfunction "VSS_3_47") (pintype "power_in"))
      (node (ref "U1") (pin "8") (pinfunction "VSSA_8") (pintype "power_in"))
      (node (ref "U5") (pin "1") (pinfunction "GND_1") (pintype "passive"))
      (node (ref "U7") (pin "2") (pinfunction "GND_2") (pintype "passive"))
      (node (ref "U7") (pin "8") (pinfunction "S_8") (pintype "passive"))
      (node (ref "USB1") (pin "5") (pinfunction "VSS_5") (pintype "passive"))
      (node (ref "USB_USART1") (pin "5") (pinfunction "VSS_5") (pintype "passive"))
      (node (ref "VR1") (pin "1") (pinfunction "GND_1") (pintype "passive"))
    )
    (net (code "42") (name "Net-(D1-PadA)") (class "Default")
      (node (ref "D1") (pin "A") (pinfunction "A_A") (pintype "passive"))
      (node (ref "R1") (pin "2") (pinfunction "2_2") (pintype "passive"))
    )
    (net (code "43") (name "Net-(D2-PadA)") (class "Default")
      (node (ref "D2") (pin "A") (pinfunction "A_A") (pintype "passive"))
      (node (ref "R22") (pin "2") (pinfunction "2_2") (pintype "passive"))
    )
    (net (code "44") (name "Net-(Q1-D)") (class "Default")
      (node (ref "OUT1") (pin "1") (pinfunction "1_1") (pintype "passive"))
      (node (ref "Q1") (pin "3") (pinfunction "D_3") (pintype "passive"))
      (node (ref "R8") (pin "2") (pinfunction "2_2") (pintype "passive"))
    )
    (net (code "45") (name "Net-(Q1-G)") (class "Default")
      (node (ref "Q1") (pin "1") (pinfunction "G_1") (pintype "passive"))
      (node (ref "R7") (pin "1") (pinfunction "1_1") (pintype "passive"))
      (node (ref "R8") (pin "1") (pinfunction "1_1") (pintype "passive"))
    )
    (net (code "46") (name "Net-(R32-Pad2)") (class "Default")
      (node (ref "R32") (pin "2") (pinfunction "2_2") (pintype "passive"))
      (node (ref "R35") (pin "1") (pinfunction "1_1") (pintype "passive"))
      (node (ref "表面电阻1") (pin "2") (pinfunction "2_2") (pintype "passive"))
    )
    (net (code "47") (name "Net-(U1A-BOOT0)") (class "Default")
      (node (ref "R15") (pin "1") (pinfunction "1_1") (pintype "passive"))
      (node (ref "U1") (pin "44") (pinfunction "BOOT0_44") (pintype "input"))
    )
    (net (code "48") (name "Net-(U1B-VBAT)") (class "Default")
      (node (ref "U1") (pin "1") (pinfunction "VBAT_1") (pintype "power_in"))
      (node (ref "U1") (pin "24") (pinfunction "VDD_1_24") (pintype "power_in"))
      (node (ref "U1") (pin "36") (pinfunction "VDD_2_36") (pintype "power_in"))
      (node (ref "U1") (pin "48") (pinfunction "VDD_3_48") (pintype "power_in"))
    )
    (net (code "49") (name "Net-(U1B-VDDA)") (class "Default")
      (node (ref "C17") (pin "2") (pinfunction "2_2") (pintype "passive"))
      (node (ref "L1") (pin "1") (pinfunction "1_1") (pintype "passive"))
      (node (ref "U1") (pin "9") (pinfunction "VDDA_9") (pintype "power_in"))
    )
    (net (code "50") (name "Net-(U2A-IN+)") (class "Default")
      (node (ref "R19") (pin "1") (pinfunction "1_1") (pintype "passive"))
      (node (ref "U2") (pin "3") (pinfunction "IN+_3") (pintype "input"))
    )
    (net (code "51") (name "Net-(U2A-IN-)") (class "Default")
      (node (ref "R11") (pin "2") (pinfunction "2_2") (pintype "passive"))
      (node (ref "R13") (pin "1") (pinfunction "1_1") (pintype "passive"))
      (node (ref "R16") (pin "1") (pinfunction "1_1") (pintype "passive"))
      (node (ref "U2") (pin "2") (pinfunction "IN-_2") (pintype "input"))
    )
    (net (code "52") (name "Net-(U2A-OUT)") (class "Default")
      (node (ref "R11") (pin "1") (pinfunction "1_1") (pintype "passive"))
      (node (ref "R17") (pin "1") (pinfunction "1_1") (pintype "passive"))
      (node (ref "U2") (pin "1") (pinfunction "OUT_1") (pintype "output"))
    )
    (net (code "53") (name "Net-(U2B-IN+)") (class "Default")
      (node (ref "R20") (pin "1") (pinfunction "1_1") (pintype "passive"))
      (node (ref "U2") (pin "5") (pinfunction "IN+_5") (pintype "input"))
    )
    (net (code "54") (name "Net-(U2B-IN-)") (class "Default")
      (node (ref "R12") (pin "2") (pinfunction "2_2") (pintype "passive"))
      (node (ref "R17") (pin "2") (pinfunction "2_2") (pintype "passive"))
      (node (ref "U2") (pin "6") (pinfunction "IN-_6") (pintype "input"))
    )
    (net (code "55") (name "Net-(U2B-OUT)") (class "Default")
      (node (ref "R12") (pin "1") (pinfunction "1_1") (pintype "passive"))
      (node (ref "R18") (pin "1") (pinfunction "1_1") (pintype "passive"))
      (node (ref "U2") (pin "7") (pinfunction "OUT_7") (pintype "output"))
    )
    (net (code "56") (name "Net-(U3A-IN+)") (class "Default")
      (node (ref "R31") (pin "1") (pinfunction "1_1") (pintype "passive"))
      (node (ref "U3") (pin "3") (pinfunction "IN+_3") (pintype "input"))
    )
    (net (code "57") (name "Net-(U3A-IN-)") (class "Default")
      (node (ref "R23") (pin "2") (pinfunction "2_2") (pintype "passive"))
      (node (ref "R25") (pin "1") (pinfunction "1_1") (pintype "passive"))
      (node (ref "R27") (pin "1") (pinfunction "1_1") (pintype "passive"))
      (node (ref "U3") (pin "2") (pinfunction "IN-_2") (pintype "input"))
    )
    (net (code "58") (name "Net-(U3A-OUT)") (class "Default")
      (node (ref "R23") (pin "1") (pinfunction "1_1") (pintype "passive"))
      (node (ref "R28") (pin "1") (pinfunction "1_1") (pintype "passive"))
      (node (ref "U3") (pin "1") (pinfunction "OUT_1") (pintype "output"))
    )
    (net (code "59") (name "Net-(U3B-IN+)") (class "Default")
      (node (ref "R33") (pin "1") (pinfunction "1_1") (pintype "passive"))
      (node (ref "U3") (pin "5") (pinfunction "IN+_5") (pintype "input"))
    )
    (net (code "60") (name "Net-(U3B-IN-)") (class "Default")
      (node (ref "R24") (pin "2") (pinfunction "2_2") (pintype "passive"))
      (node (ref "R28") (pin "2") (pinfunction "2_2") (pintype "passive"))
      (node (ref "U3") (pin "6") (pinfunction "IN-_6") (pintype "input"))
    )
    (net (code "61") (name "Net-(U3B-OUT)") (class "Default")
      (node (ref "R24") (pin "1") (pinfunction "1_1") (pintype "passive"))
      (node (ref "R29") (pin "1") (pinfunction "1_1") (pintype "passive"))
      (node (ref "U3") (pin "7") (pinfunction "OUT_7") (pintype "output"))
    )
    (net (code "62") (name "Net-(U4A-IN+)") (class "Default")
      (node (ref "R35") (pin "2") (pinfunction "2_2") (pintype "passive"))
      (node (ref "U4") (pin "3") (pinfunction "IN+_3") (pintype "input"))
    )
    (net (code "63") (name "Net-(U4A-IN-)") (class "Default")
      (node (ref "R26") (pin "1") (pinfunction "1_1") (pintype "passive"))
      (node (ref "R30") (pin "2") (pinfunction "2_2") (pintype "passive"))
      (node (ref "U4") (pin "2") (pinfunction "IN-_2") (pintype "input"))
    )
    (net (code "64") (name "Net-(U4A-OUT)") (class "Default")
      (node (ref "R26") (pin "2") (pinfunction "2_2") (pintype "passive"))
      (node (ref "U4") (pin "1") (pinfunction "OUT_1") (pintype "output"))
      (node (ref "U4") (pin "5") (pinfunction "IN+_5") (pintype "input"))
    )
    (net (code "65") (name "Net-(U5-V3.3)") (class "Default")
      (node (ref "C20") (pin "1") (pinfunction "1_1") (pintype "passive"))
      (node (ref "U5") (pin "4") (pinfunction "V3.3_4") (pintype "passive"))
    )
    (net (code "66") (name "Net-(U5-XI)") (class "Default")
      (node (ref "C22") (pin "2") (pinfunction "2_2") (pintype "passive"))
      (node (ref "U5") (pin "7") (pinfunction "XI_7") (pintype "passive"))
      (node (ref "Y2") (pin "1") (pinfunction "OSC1_1") (pintype "passive"))
    )
    (net (code "67") (name "Net-(U5-XO)") (class "Default")
      (node (ref "C23") (pin "2") (pinfunction "2_2") (pintype "passive"))
      (node (ref "U5") (pin "8") (pinfunction "XO_8") (pintype "passive"))
      (node (ref "Y2") (pin "3") (pinfunction "OSC2_3") (pintype "passive"))
    )
    (net (code "68") (name "Net-(U6A-IN+)") (class "Default")
      (node (ref "R44") (pin "1") (pinfunction "1_1") (pintype "passive"))
      (node (ref "U6") (pin "3") (pinfunction "IN+_3") (pintype "input"))
    )
    (net (code "69") (name "Net-(U6A-IN-)") (class "Default")
      (node (ref "R36") (pin "1") (pinfunction "1_1") (pintype "passive"))
      (node (ref "R42") (pin "1") (pinfunction "1_1") (pintype "passive"))
      (node (ref "U6") (pin "2") (pinfunction "IN-_2") (pintype "input"))
    )
    (net (code "70") (name "Net-(U6A-OUT)") (class "Default")
      (node (ref "R36") (pin "2") (pinfunction "2_2") (pintype "passive"))
      (node (ref "R43") (pin "2") (pinfunction "2_2") (pintype "passive"))
      (node (ref "U6") (pin "1") (pinfunction "OUT_1") (pintype "output"))
    )
    (net (code "71") (name "Net-(U6B-IN+)") (class "Default")
      (node (ref "R45") (pin "1") (pinfunction "1_1") (pintype "passive"))
      (node (ref "U6") (pin "5") (pinfunction "IN+_5") (pintype "input"))
    )
    (net (code "72") (name "Net-(U6B-IN-)") (class "Default")
      (node (ref "R37") (pin "2") (pinfunction "2_2") (pintype "passive"))
      (node (ref "R40") (pin "1") (pinfunction "1_1") (pintype "passive"))
      (node (ref "R43") (pin "1") (pinfunction "1_1") (pintype "passive"))
      (node (ref "U6") (pin "6") (pinfunction "IN-_6") (pintype "input"))
    )
    (net (code "73") (name "SGND") (class "Default")
      (node (ref "*2") (pin "2") (pinfunction "ANODE_2") (pintype "passive"))
      (node (ref "*3") (pin "5") (pinfunction "AGND_5") (pintype "passive"))
      (node (ref "A1") (pin "5") (pinfunction "0V_5") (pintype "passive"))
      (node (ref "C21") (pin "2") (pinfunction "2_2") (pintype "passive"))
      (node (ref "C24") (pin "1") (pinfunction "1_1") (pintype "passive"))
      (node (ref "C26") (pin "2") (pinfunction "2_2") (pintype "passive"))
      (node (ref "C29") (pin "2") (pinfunction "2_2") (pintype "passive"))
      (node (ref "DA1") (pin "2") (pinfunction "2_2") (pintype "passive"))
      (node (ref "L2") (pin "2") (pinfunction "2_2") (pintype "passive"))
      (node (ref "R19") (pin "2") (pinfunction "2_2") (pintype "passive"))
      (node (ref "R20") (pin "2") (pinfunction "2_2") (pintype "passive"))
      (node (ref "R21") (pin "1") (pinfunction "1_1") (pintype "passive"))
      (node (ref "R30") (pin "1") (pinfunction "1_1") (pintype "passive"))
      (node (ref "R31") (pin "2") (pinfunction "2_2") (pintype "passive"))
      (node (ref "R33") (pin "2") (pinfunction "2_2") (pintype "passive"))
      (node (ref "R34") (pin "1") (pinfunction "1_1") (pintype "passive"))
      (node (ref "R44") (pin "2") (pinfunction "2_2") (pintype "passive"))
      (node (ref "R45") (pin "2") (pinfunction "2_2") (pintype "passive"))
      (node (ref "U4") (pin "4") (pinfunction "V-_4") (pintype "power_in"))
      (node (ref "表面电阻1") (pin "1") (pinfunction "1_1") (pintype "passive"))
    )
    (net (code "74") (name "unconnected-(*2-NC-Pad3)") (class "Default")
      (node (ref "*2") (pin "3") (pinfunction "NC_3") (pintype "passive"))
    )
    (net (code "75") (name "unconnected-(*3-DOUT-Pad4)") (class "Default")
      (node (ref "*3") (pin "4") (pinfunction "DOUT_4") (pintype "passive"))
    )
    (net (code "76") (name "unconnected-(*4-NC-Pad3)") (class "Default")
      (node (ref "*4") (pin "3") (pinfunction "NC_3") (pintype "passive"))
    )
    (net (code "77") (name "unconnected-(*4-NC-Pad4)") (class "Default")
      (node (ref "*4") (pin "4") (pinfunction "NC_4") (pintype "passive"))
    )
    (net (code "78") (name "unconnected-(Force Sensor1-Pad1)") (class "Default")
      (node (ref "Force Sensor1") (pin "1") (pinfunction "1_1") (pintype "passive"))
    )
    (net (code "79") (name "unconnected-(Force Sensor1-Pad2)") (class "Default")
      (node (ref "Force Sensor1") (pin "2") (pinfunction "2_2") (pintype "passive"))
    )
    (net (code "80") (name "unconnected-(Force Sensor1-Pad3)") (class "Default")
      (node (ref "Force Sensor1") (pin "3") (pinfunction "3_3") (pintype "passive"))
    )
    (net (code "81") (name "unconnected-(Force Sensor1-Pad4)") (class "Default")
      (node (ref "Force Sensor1") (pin "4") (pinfunction "4_4") (pintype "passive"))
    )
    (net (code "82") (name "unconnected-(P1-Pad3)") (class "Default")
      (node (ref "P1") (pin "3") (pinfunction "3_3") (pintype "passive"))
    )
    (net (code "83") (name "unconnected-(P1-Pad4)") (class "Default")
      (node (ref "P1") (pin "4") (pinfunction "4_4") (pintype "passive"))
    )
    (net (code "84") (name "unconnected-(T1-Pad1)") (class "Default")
      (node (ref "T1") (pin "1") (pinfunction "1_1") (pintype "passive"))
    )
    (net (code "85") (name "unconnected-(T2-Pad1)") (class "Default")
      (node (ref "T2") (pin "1") (pinfunction "1_1") (pintype "passive"))
    )
    (net (code "86") (name "unconnected-(T3-Pad1)") (class "Default")
      (node (ref "T3") (pin "1") (pinfunction "1_1") (pintype "passive"))
    )
    (net (code "87") (name "unconnected-(T4-Pad1)") (class "Default")
      (node (ref "T4") (pin "1") (pinfunction "1_1") (pintype "passive"))
    )
    (net (code "88") (name "unconnected-(U1A-PA4-Pad14)") (class "Default")
      (node (ref "U1") (pin "14") (pinfunction "PA4_14") (pintype "bidirectional"))
    )
    (net (code "89") (name "unconnected-(U1A-PA5-Pad15)") (class "Default")
      (node (ref "U1") (pin "15") (pinfunction "PA5_15") (pintype "bidirectional"))
    )
    (net (code "90") (name "unconnected-(U1A-PA6-Pad16)") (class "Default")
      (node (ref "U1") (pin "16") (pinfunction "PA6_16") (pintype "bidirectional"))
    )
    (net (code "91") (name "unconnected-(U1A-PA7-Pad17)") (class "Default")
      (node (ref "U1") (pin "17") (pinfunction "PA7_17") (pintype "bidirectional"))
    )
    (net (code "92") (name "unconnected-(U1A-PA8-Pad29)") (class "Default")
      (node (ref "U1") (pin "29") (pinfunction "PA8_29") (pintype "bidirectional"))
    )
    (net (code "93") (name "unconnected-(U1A-PB1-Pad19)") (class "Default")
      (node (ref "U1") (pin "19") (pinfunction "PB1_19") (pintype "bidirectional"))
    )
    (net (code "94") (name "unconnected-(U1A-PB2-Pad20)") (class "Default")
      (node (ref "U1") (pin "20") (pinfunction "PB2_20") (pintype "bidirectional"))
    )
    (net (code "95") (name "unconnected-(U1A-PB3-Pad39)") (class "Default")
      (node (ref "U1") (pin "39") (pinfunction "PB3_39") (pintype "bidirectional"))
    )
    (net (code "96") (name "unconnected-(U1A-PB4-Pad40)") (class "Default")
      (node (ref "U1") (pin "40") (pinfunction "PB4_40") (pintype "bidirectional"))
    )
    (net (code "97") (name "unconnected-(U1A-PB5-Pad41)") (class "Default")
      (node (ref "U1") (pin "41") (pinfunction "PB5_41") (pintype "bidirectional"))
    )
    (net (code "98") (name "unconnected-(U1A-PB10-Pad21)") (class "Default")
      (node (ref "U1") (pin "21") (pinfunction "PB10_21") (pintype "bidirectional"))
    )
    (net (code "99") (name "unconnected-(U1A-PB11-Pad22)") (class "Default")
      (node (ref "U1") (pin "22") (pinfunction "PB11_22") (pintype "bidirectional"))
    )
    (net (code "100") (name "unconnected-(U1A-PB12-Pad25)") (class "Default")
      (node (ref "U1") (pin "25") (pinfunction "PB12_25") (pintype "bidirectional"))
    )
    (net (code "101") (name "unconnected-(U1A-PB13-Pad26)") (class "Default")
      (node (ref "U1") (pin "26") (pinfunction "PB13_26") (pintype "bidirectional"))
    )
    (net (code "102") (name "unconnected-(U1A-PB14-Pad27)") (class "Default")
      (node (ref "U1") (pin "27") (pinfunction "PB14_27") (pintype "bidirectional"))
    )
    (net (code "103") (name "unconnected-(U1A-PB15-Pad28)") (class "Default")
      (node (ref "U1") (pin "28") (pinfunction "PB15_28") (pintype "bidirectional"))
    )
    (net (code "104") (name "unconnected-(U1A-PC13-TAMPER-RTC-Pad2)") (class "Default")
      (node (ref "U1") (pin "2") (pinfunction "PC13-TAMPER-RTC_2") (pintype "bidirectional"))
    )
    (net (code "105") (name "unconnected-(U1A-PC14-OSC32_IN-Pad3)") (class "Default")
      (node (ref "U1") (pin "3") (pinfunction "PC14-OSC32_IN_3") (pintype "bidirectional"))
    )
    (net (code "106") (name "unconnected-(U1A-PC15-OSC32_OUT-Pad4)") (class "Default")
      (node (ref "U1") (pin "4") (pinfunction "PC15-OSC32_OUT_4") (pintype "bidirectional"))
    )
    (net (code "107") (name "unconnected-(U4B-V+-Pad8)") (class "Default")
      (node (ref "U4") (pin "8") (pinfunction "V+_8") (pintype "power_in"))
    )
    (net (code "108") (name "unconnected-(U4B-V--Pad4)") (class "Default")
      (node (ref "U4") (pin "4") (pinfunction "V-_4") (pintype "power_in"))
    )
    (net (code "109") (name "unconnected-(U5-CTS#-Pad9)") (class "Default")
      (node (ref "U5") (pin "9") (pinfunction "CTS#_9") (pintype "passive"))
    )
    (net (code "110") (name "unconnected-(U5-DCD#-Pad13)") (class "Default")
      (node (ref "U5") (pin "13") (pinfunction "DCD#_13") (pintype "passive"))
    )
    (net (code "111") (name "unconnected-(U5-DSR#-Pad10)") (class "Default")
      (node (ref "U5") (pin "10") (pinfunction "DSR#_10") (pintype "passive"))
    )
    (net (code "112") (name "unconnected-(U5-DTR#-Pad12)") (class "Default")
      (node (ref "U5") (pin "12") (pinfunction "DTR#_12") (pintype "passive"))
    )
    (net (code "113") (name "unconnected-(U5-R232-Pad15)") (class "Default")
      (node (ref "U5") (pin "15") (pinfunction "R232_15") (pintype "passive"))
    )
    (net (code "114") (name "unconnected-(U5-RI#-Pad14)") (class "Default")
      (node (ref "U5") (pin "14") (pinfunction "RI#_14") (pintype "passive"))
    )
    (net (code "115") (name "unconnected-(U5-RTS#-Pad11)") (class "Default")
      (node (ref "U5") (pin "11") (pinfunction "RTS#_11") (pintype "passive"))
    )
    (net (code "116") (name "unconnected-(U7-n.c.-Pad5)") (class "Default")
      (node (ref "U7") (pin "5") (pinfunction "n.c._5") (pintype "passive"))
    )
    (net (code "117") (name "unconnected-(USB1-ID-Pad4)") (class "Default")
      (node (ref "USB1") (pin "4") (pinfunction "ID_4") (pintype "passive"))
    )
    (net (code "118") (name "unconnected-(USB_USART1-ID-Pad4)") (class "Default")
      (node (ref "USB_USART1") (pin "4") (pinfunction "ID_4") (pintype "passive"))
    )
  )
)
